# OpenUltrasound_Pulser.net
KiCad netlist of a schematic drawn in Altium Designer
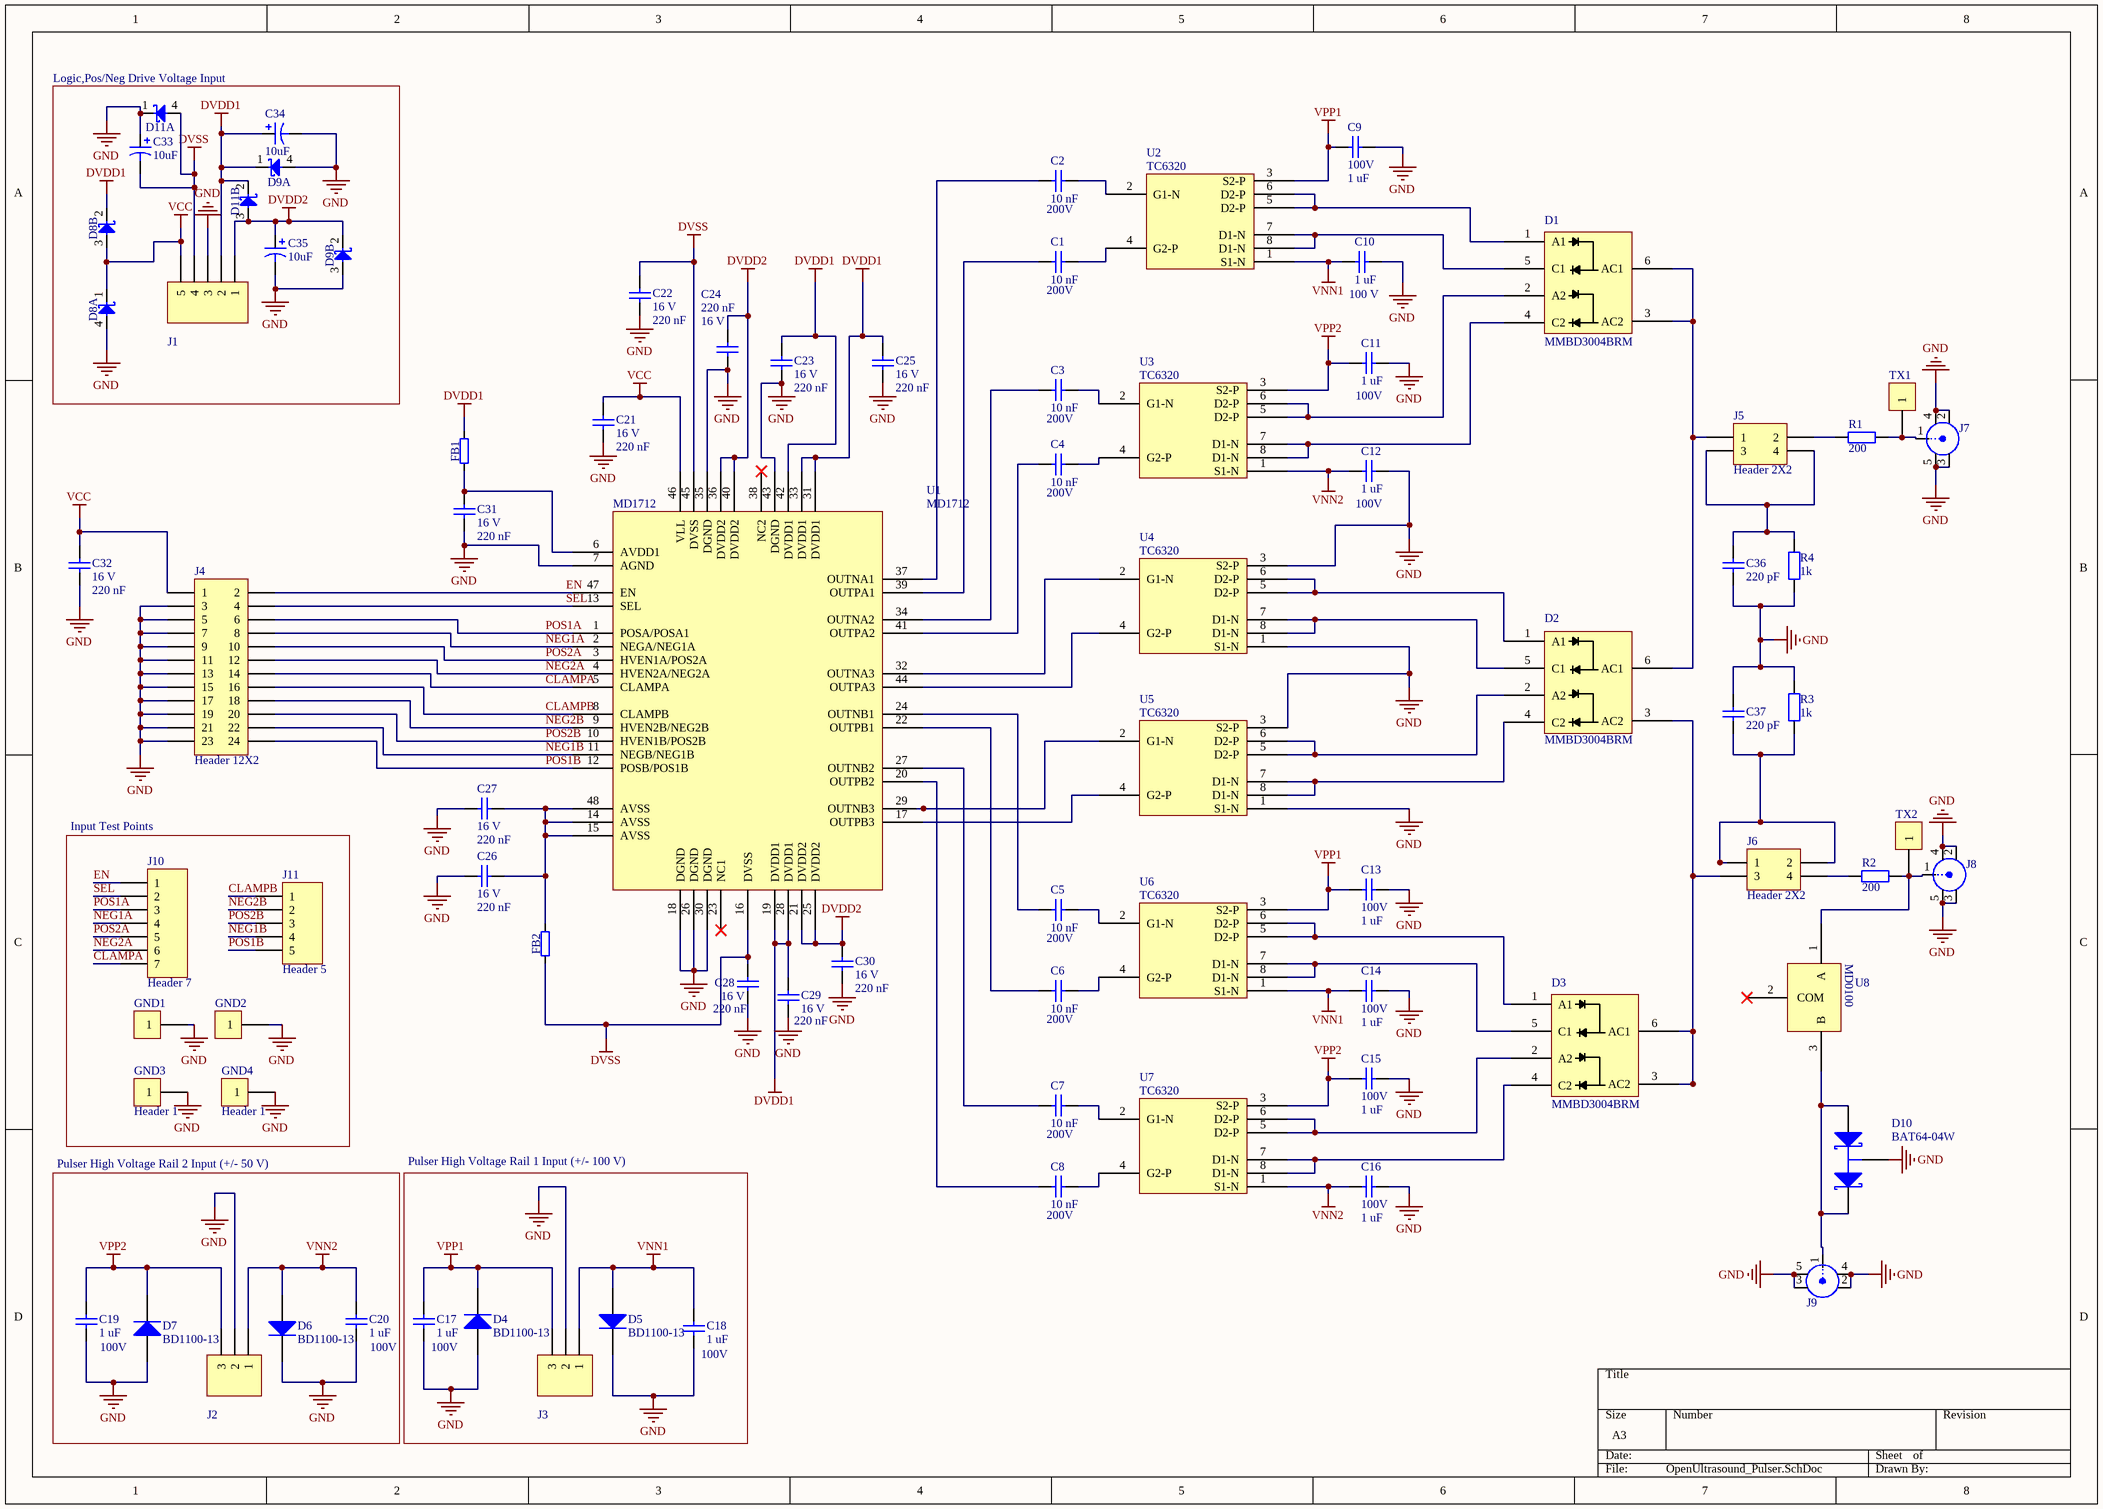
[diagram p0: OpenUltrasound_Pulser.SchDoc]

(export (version "E")
  (design (tool "Eeschema 10.0.6"))
  (components
    (comp (ref "C1")
      (value "200V")
      (footprint "CAP1608X100N")
      (description "Capacitor")
      (fields (field (name "ALTIUM_VALUE") "10 nF"))
      (libsource (lib "OpenUltrasound_Components") (part "CAP0603"))
    )
    (comp (ref "C2")
      (value "200V")
      (footprint "CAP1608X100N")
      (description "Capacitor")
      (fields (field (name "ALTIUM_VALUE") "10 nF"))
      (libsource (lib "OpenUltrasound_Components") (part "CAP0603"))
    )
    (comp (ref "C3")
      (value "200V")
      (footprint "CAP1608X100N")
      (description "Capacitor")
      (fields (field (name "ALTIUM_VALUE") "10 nF"))
      (libsource (lib "OpenUltrasound_Components") (part "CAP0603"))
    )
    (comp (ref "C4")
      (value "200V")
      (footprint "CAP1608X100N")
      (description "Capacitor")
      (fields (field (name "ALTIUM_VALUE") "10 nF"))
      (libsource (lib "OpenUltrasound_Components") (part "CAP0603"))
    )
    (comp (ref "C5")
      (value "200V")
      (footprint "CAP1608X100N")
      (description "Capacitor")
      (fields (field (name "ALTIUM_VALUE") "10 nF"))
      (libsource (lib "OpenUltrasound_Components") (part "CAP0603"))
    )
    (comp (ref "C6")
      (value "200V")
      (footprint "CAP1608X100N")
      (description "Capacitor")
      (fields (field (name "ALTIUM_VALUE") "10 nF"))
      (libsource (lib "OpenUltrasound_Components") (part "CAP0603"))
    )
    (comp (ref "C7")
      (value "200V")
      (footprint "CAP1608X100N")
      (description "Capacitor")
      (fields (field (name "ALTIUM_VALUE") "10 nF"))
      (libsource (lib "OpenUltrasound_Components") (part "CAP0603"))
    )
    (comp (ref "C8")
      (value "200V")
      (footprint "CAP1608X100N")
      (description "Capacitor")
      (fields (field (name "ALTIUM_VALUE") "10 nF"))
      (libsource (lib "OpenUltrasound_Components") (part "CAP0603"))
    )
    (comp (ref "C9")
      (value "100V")
      (footprint "CAP3216X180N")
      (description "Capacitor")
      (fields (field (name "ALTIUM_VALUE") "1 uF"))
      (libsource (lib "OpenUltrasound_Components") (part "CAP1206"))
    )
    (comp (ref "C10")
      (value "100 V")
      (footprint "CAP3216X180N")
      (description "Capacitor")
      (fields (field (name "ALTIUM_VALUE") "1 uF"))
      (libsource (lib "OpenUltrasound_Components") (part "CAP1206"))
    )
    (comp (ref "C11")
      (value "100V")
      (footprint "CAP3216X180N")
      (description "Capacitor")
      (fields (field (name "ALTIUM_VALUE") "1 uF"))
      (libsource (lib "OpenUltrasound_Components") (part "CAP1206"))
    )
    (comp (ref "C12")
      (value "100V")
      (footprint "CAP3216X180N")
      (description "Capacitor")
      (fields (field (name "ALTIUM_VALUE") "1 uF"))
      (libsource (lib "OpenUltrasound_Components") (part "CAP1206"))
    )
    (comp (ref "C13")
      (value "100V")
      (footprint "CAP3216X180N")
      (description "Capacitor")
      (fields (field (name "ALTIUM_VALUE") "1 uF"))
      (libsource (lib "OpenUltrasound_Components") (part "CAP1206"))
    )
    (comp (ref "C14")
      (value "100V")
      (footprint "CAP3216X180N")
      (description "Capacitor")
      (fields (field (name "ALTIUM_VALUE") "1 uF"))
      (libsource (lib "OpenUltrasound_Components") (part "CAP1206"))
    )
    (comp (ref "C15")
      (value "100V")
      (footprint "CAP3216X180N")
      (description "Capacitor")
      (fields (field (name "ALTIUM_VALUE") "1 uF"))
      (libsource (lib "OpenUltrasound_Components") (part "CAP1206"))
    )
    (comp (ref "C16")
      (value "100V")
      (footprint "CAP3216X180N")
      (description "Capacitor")
      (fields (field (name "ALTIUM_VALUE") "1 uF"))
      (libsource (lib "OpenUltrasound_Components") (part "CAP1206"))
    )
    (comp (ref "C17")
      (value "100V")
      (footprint "CAP3216X180N")
      (description "Capacitor")
      (fields (field (name "ALTIUM_VALUE") "1 uF"))
      (libsource (lib "OpenUltrasound_Components") (part "CAP1206"))
    )
    (comp (ref "C18")
      (value "100V")
      (footprint "CAP3216X180N")
      (description "Capacitor")
      (fields (field (name "ALTIUM_VALUE") "1 uF"))
      (libsource (lib "OpenUltrasound_Components") (part "CAP1206"))
    )
    (comp (ref "C19")
      (value "100V")
      (footprint "CAP3216X180N")
      (description "Capacitor")
      (fields (field (name "ALTIUM_VALUE") "1 uF"))
      (libsource (lib "OpenUltrasound_Components") (part "CAP1206"))
    )
    (comp (ref "C20")
      (value "100V")
      (footprint "CAP3216X180N")
      (description "Capacitor")
      (fields (field (name "ALTIUM_VALUE") "1 uF"))
      (libsource (lib "OpenUltrasound_Components") (part "CAP1206"))
    )
    (comp (ref "C21")
      (value "16 V")
      (footprint "CAP1608X100N")
      (description "Capacitor")
      (fields (field (name "ALTIUM_VALUE") "220 nF"))
      (libsource (lib "OpenUltrasound_Components") (part "CAP0603"))
    )
    (comp (ref "C22")
      (value "16 V")
      (footprint "CAP1608X100N")
      (description "Capacitor")
      (fields (field (name "ALTIUM_VALUE") "220 nF"))
      (libsource (lib "OpenUltrasound_Components") (part "CAP0603"))
    )
    (comp (ref "C23")
      (value "16 V")
      (footprint "CAP1608X100N")
      (description "Capacitor")
      (fields (field (name "ALTIUM_VALUE") "220 nF"))
      (libsource (lib "OpenUltrasound_Components") (part "CAP0603"))
    )
    (comp (ref "C24")
      (value "16 V")
      (footprint "CAP1608X100N")
      (description "Capacitor")
      (fields (field (name "ALTIUM_VALUE") "220 nF"))
      (libsource (lib "OpenUltrasound_Components") (part "CAP0603"))
    )
    (comp (ref "C25")
      (value "16 V")
      (footprint "CAP1608X100N")
      (description "Capacitor")
      (fields (field (name "ALTIUM_VALUE") "220 nF"))
      (libsource (lib "OpenUltrasound_Components") (part "CAP0603"))
    )
    (comp (ref "C26")
      (value "16 V")
      (footprint "CAP1608X100N")
      (description "Capacitor")
      (fields (field (name "ALTIUM_VALUE") "220 nF"))
      (libsource (lib "OpenUltrasound_Components") (part "CAP0603"))
    )
    (comp (ref "C27")
      (value "16 V")
      (footprint "CAP1608X100N")
      (description "Capacitor")
      (fields (field (name "ALTIUM_VALUE") "220 nF"))
      (libsource (lib "OpenUltrasound_Components") (part "CAP0603"))
    )
    (comp (ref "C28")
      (value "16 V")
      (footprint "CAP1608X100N")
      (description "Capacitor")
      (fields (field (name "ALTIUM_VALUE") "220 nF"))
      (libsource (lib "OpenUltrasound_Components") (part "CAP0603"))
    )
    (comp (ref "C29")
      (value "16 V")
      (footprint "CAP1608X100N")
      (description "Capacitor")
      (fields (field (name "ALTIUM_VALUE") "220 nF"))
      (libsource (lib "OpenUltrasound_Components") (part "CAP0603"))
    )
    (comp (ref "C30")
      (value "16 V")
      (footprint "CAP1608X100N")
      (description "Capacitor")
      (fields (field (name "ALTIUM_VALUE") "220 nF"))
      (libsource (lib "OpenUltrasound_Components") (part "CAP0603"))
    )
    (comp (ref "C31")
      (value "16 V")
      (footprint "CAP1608X100N")
      (description "Capacitor")
      (fields (field (name "ALTIUM_VALUE") "220 nF"))
      (libsource (lib "OpenUltrasound_Components") (part "CAP0603"))
    )
    (comp (ref "C32")
      (value "16 V")
      (footprint "CAP1608X100N")
      (description "Capacitor")
      (fields (field (name "ALTIUM_VALUE") "220 nF"))
      (libsource (lib "OpenUltrasound_Components") (part "CAP0603"))
    )
    (comp (ref "C33")
      (value "10uF")
      (footprint "CAPAE530X540N")
      (description "Polarized Capacitor (Radial Can SMD)")
      (libsource (lib "OpenUltrasound_Components") (part "CAP POL"))
    )
    (comp (ref "C34")
      (value "10uF")
      (footprint "CAPAE530X540N")
      (description "Polarized Capacitor (Radial Can SMD)")
      (libsource (lib "OpenUltrasound_Components") (part "CAP POL"))
    )
    (comp (ref "C35")
      (value "10uF")
      (footprint "CAPAE530X540N")
      (description "Polarized Capacitor (Radial Can SMD)")
      (libsource (lib "OpenUltrasound_Components") (part "CAP POL"))
    )
    (comp (ref "C36")
      (value "220 pF")
      (footprint "CAP1608X100N")
      (description "Capacitor")
      (libsource (lib "OpenUltrasound_Components") (part "CAP0603"))
    )
    (comp (ref "C37")
      (value "220 pF")
      (footprint "CAP1608X100N")
      (description "Capacitor")
      (libsource (lib "OpenUltrasound_Components") (part "CAP0603"))
    )
    (comp (ref "D1")
      (value "MMBD3004BRM")
      (footprint "SOT26A-6AN")
      (description "High Voltage Surface Mount Switching Diode Array")
      (libsource (lib "OpenUltrasound_Components") (part "MMBD3004BRM"))
    )
    (comp (ref "D2")
      (value "MMBD3004BRM")
      (footprint "SOT26A-6AN")
      (description "High Voltage Surface Mount Switching Diode Array")
      (libsource (lib "OpenUltrasound_Components") (part "MMBD3004BRM"))
    )
    (comp (ref "D3")
      (value "MMBD3004BRM")
      (footprint "SOT26A-6AN")
      (description "High Voltage Surface Mount Switching Diode Array")
      (libsource (lib "OpenUltrasound_Components") (part "MMBD3004BRM"))
    )
    (comp (ref "D4")
      (value "BD1100-13")
      (footprint "ST DO214AC SMA")
      (libsource (lib "OpenUltrasound_Components") (part "BD1100-13"))
    )
    (comp (ref "D5")
      (value "BD1100-13")
      (footprint "ST DO214AC SMA")
      (libsource (lib "OpenUltrasound_Components") (part "BD1100-13"))
    )
    (comp (ref "D6")
      (value "BD1100-13")
      (footprint "ST DO214AC SMA")
      (libsource (lib "OpenUltrasound_Components") (part "BD1100-13"))
    )
    (comp (ref "D7")
      (value "BD1100-13")
      (footprint "ST DO214AC SMA")
      (libsource (lib "OpenUltrasound_Components") (part "BD1100-13"))
    )
    (comp (ref "D8")
      (value "~")
      (footprint "SOT143L")
      (description "Serial Schottky Diode")
      (libsource (lib "OpenUltrasound_Components") (part "Diode Schottky x2 A4C1_A3C2"))
    )
    (comp (ref "D9")
      (value "~")
      (footprint "SOT143L")
      (description "Serial Schottky Diode")
      (libsource (lib "OpenUltrasound_Components") (part "Diode Schottky x2 A4C1_A3C2"))
    )
    (comp (ref "D10")
      (value "BAT64-04W")
      (footprint "SOT-323")
      (description "Silicon AF Schottky Diode for Low-Loss, Fast-Recovery, Meter Protection")
      (fields (field (name "PUBLISHER") "Altium Limited"))
      (libsource (lib "OpenUltrasound_Components") (part "BAT64-04W"))
    )
    (comp (ref "D11")
      (value "~")
      (footprint "SOT143L")
      (description "Serial Schottky Diode")
      (libsource (lib "OpenUltrasound_Components") (part "Diode Schottky x2 A4C1_A3C2"))
    )
    (comp (ref "FB1")
      (value "~")
      (footprint "CAP1608X85N")
      (description "Ferrite Bead")
      (libsource (lib "OpenUltrasound_Components") (part "Ferrite Bead"))
    )
    (comp (ref "FB2")
      (value "~")
      (footprint "CAP1608X85N")
      (description "Ferrite Bead")
      (libsource (lib "OpenUltrasound_Components") (part "Ferrite Bead"))
    )
    (comp (ref "GND1")
      (value "Header 1")
      (footprint "HDR1X1")
      (description "Header, 1-Pin")
      (fields (field (name "PUBLISHER") "Altium Limited"))
      (libsource (lib "") (part "Header 1_1"))
    )
    (comp (ref "GND2")
      (value "Header 1")
      (footprint "HDR1X1")
      (description "Header, 1-Pin")
      (fields (field (name "PUBLISHER") "Altium Limited"))
      (libsource (lib "") (part "Header 1_1"))
    )
    (comp (ref "GND3")
      (value "Header 1")
      (footprint "HDR1X1")
      (description "Header, 1-Pin")
      (fields (field (name "PUBLISHER") "Altium Limited"))
      (libsource (lib "") (part "Header 1_1"))
    )
    (comp (ref "GND4")
      (value "Header 1")
      (footprint "HDR1X1")
      (description "Header, 1-Pin")
      (fields (field (name "PUBLISHER") "Altium Limited"))
      (libsource (lib "") (part "Header 1_1"))
    )
    (comp (ref "J1")
      (value "Header 5 - pin")
      (footprint "B5B-XH-A")
      (description "Header, 5-pin")
      (fields (field (name "PUBLISHER") "Altium Limited"))
      (libsource (lib "OpenUltrasound_Components") (part "B5B-XH-A"))
    )
    (comp (ref "J2")
      (value "Header 3 - pin")
      (footprint "B3B-XH-A")
      (description "Header, 3-pin")
      (fields (field (name "PUBLISHER") "Altium Limited"))
      (libsource (lib "OpenUltrasound_Components") (part "B3B-XH-A"))
    )
    (comp (ref "J3")
      (value "Header 3 - pin")
      (footprint "B3B-XH-A")
      (description "Header, 3-pin")
      (fields (field (name "PUBLISHER") "Altium Limited"))
      (libsource (lib "OpenUltrasound_Components") (part "B3B-XH-A"))
    )
    (comp (ref "J4")
      (value "Header 12X2")
      (footprint "HDR2X12")
      (description "Header, 12-Pin, Dual row")
      (fields (field (name "PUBLISHER") "Altium Limited"))
      (libsource (lib "OpenUltrasound_Components") (part "Header 12X2"))
    )
    (comp (ref "J5")
      (value "Header 2X2")
      (footprint "HDR2X2")
      (description "Header, 2-Pin, Dual row")
      (fields (field (name "PUBLISHER") "Altium Limited"))
      (libsource (lib "OpenUltrasound_Components") (part "Header 2X2"))
    )
    (comp (ref "J6")
      (value "Header 2X2")
      (footprint "HDR2X2")
      (description "Header, 2-Pin, Dual row")
      (fields (field (name "PUBLISHER") "Altium Limited"))
      (libsource (lib "OpenUltrasound_Components") (part "Header 2X2"))
    )
    (comp (ref "J7")
      (value "SMA_EDGE_MOUNT")
      (footprint "SMA-J-P-X-ST-EM1")
      (description "BNC Elbow Connector")
      (fields (field (name "PUBLISHER") "Altium Limited"))
      (libsource (lib "OpenUltrasound_Components") (part "SMA_EDGE_MOUNT"))
    )
    (comp (ref "J8")
      (value "SMA_EDGE_MOUNT")
      (footprint "SMA-J-P-X-ST-EM1")
      (description "BNC Elbow Connector")
      (fields (field (name "PUBLISHER") "Altium Limited"))
      (libsource (lib "OpenUltrasound_Components") (part "SMA_EDGE_MOUNT"))
    )
    (comp (ref "J9")
      (value "SMA_EDGE_MOUNT")
      (footprint "SMA-J-P-X-ST-EM1")
      (description "BNC Elbow Connector")
      (fields (field (name "PUBLISHER") "Altium Limited"))
      (libsource (lib "OpenUltrasound_Components") (part "SMA_EDGE_MOUNT"))
    )
    (comp (ref "J10")
      (value "Header 7")
      (footprint "HDR1X7")
      (description "Header, 7-Pin")
      (fields (field (name "PUBLISHER") "Altium Limited"))
      (libsource (lib "OpenUltrasound_Components") (part "Header 7"))
    )
    (comp (ref "J11")
      (value "Header 5")
      (footprint "HDR1X5")
      (description "Header, 5-Pin")
      (fields (field (name "PUBLISHER") "Altium Limited"))
      (libsource (lib "OpenUltrasound_Components") (part "Header 5"))
    )
    (comp (ref "R1")
      (value "200")
      (footprint "RESC2012X70N-0805")
      (description "Resistor")
      (libsource (lib "OpenUltrasound_Components") (part "RES0805"))
    )
    (comp (ref "R2")
      (value "200")
      (footprint "RESC2012X70N-0805")
      (description "Resistor")
      (libsource (lib "OpenUltrasound_Components") (part "RES0805"))
    )
    (comp (ref "R3")
      (value "1k")
      (footprint "RESC3216X80N-1206")
      (description "Resistor")
      (libsource (lib "OpenUltrasound_Components") (part "RES1206"))
    )
    (comp (ref "R4")
      (value "1k")
      (footprint "RESC3216X80N-1206")
      (description "Resistor")
      (libsource (lib "OpenUltrasound_Components") (part "RES1206"))
    )
    (comp (ref "TX1")
      (value "Header 1")
      (footprint "HDR1X1")
      (description "Header, 1-Pin")
      (fields (field (name "PUBLISHER") "Altium Limited"))
      (libsource (lib "OpenUltrasound_Components") (part "Header 1"))
    )
    (comp (ref "TX2")
      (value "Header 1")
      (footprint "HDR1X1")
      (description "Header, 1-Pin")
      (fields (field (name "PUBLISHER") "Altium Limited"))
      (libsource (lib "OpenUltrasound_Components") (part "Header 1"))
    )
    (comp (ref "U1")
      (value "MD1712")
      (footprint "OpenUltrasound_PcbLib:LQFP-48")
      (description "High Speed, Integrated Ultrasound Driver IC")
      (libsource (lib "OpenUltrasound_Schlib") (part "MD1712"))
    )
    (comp (ref "U2")
      (value "TC6320")
      (footprint "OpenUltrasound_PcbLib:SOIC127P600X175-8N")
      (libsource (lib "OpenUltrasound_Components") (part "TC6320"))
    )
    (comp (ref "U3")
      (value "TC6320")
      (footprint "OpenUltrasound_PcbLib:SOIC127P600X175-8N")
      (libsource (lib "OpenUltrasound_Components") (part "TC6320"))
    )
    (comp (ref "U4")
      (value "TC6320")
      (footprint "OpenUltrasound_PcbLib:SOIC127P600X175-8N")
      (libsource (lib "OpenUltrasound_Components") (part "TC6320"))
    )
    (comp (ref "U5")
      (value "TC6320")
      (footprint "OpenUltrasound_PcbLib:SOIC127P600X175-8N")
      (libsource (lib "OpenUltrasound_Components") (part "TC6320"))
    )
    (comp (ref "U6")
      (value "TC6320")
      (footprint "OpenUltrasound_PcbLib:SOIC127P600X175-8N")
      (libsource (lib "OpenUltrasound_Components") (part "TC6320"))
    )
    (comp (ref "U7")
      (value "TC6320")
      (footprint "OpenUltrasound_PcbLib:SOIC127P600X175-8N")
      (libsource (lib "OpenUltrasound_Components") (part "TC6320"))
    )
    (comp (ref "U8")
      (value "MD0100")
      (footprint "SOT89")
      (description "High voltage protection T/R switch")
      (libsource (lib "OpenUltrasound_Components") (part "MD0100"))
    )
  )
  (nets
    (net (code "1") (name "/CLAMPA") (class "Default")
      (node (ref "J10") (pin "7") (pinfunction "7_7") (pintype "passive"))
      (node (ref "J4") (pin "14") (pinfunction "14_14") (pintype "passive"))
      (node (ref "U1") (pin "5") (pinfunction "CLAMPA_5") (pintype "passive"))
    )
    (net (code "2") (name "/CLAMPB") (class "Default")
      (node (ref "J11") (pin "1") (pinfunction "1_1") (pintype "passive"))
      (node (ref "J4") (pin "16") (pinfunction "16_16") (pintype "passive"))
      (node (ref "U1") (pin "8") (pinfunction "CLAMPB_8") (pintype "passive"))
    )
    (net (code "3") (name "/EN") (class "Default")
      (node (ref "J10") (pin "1") (pinfunction "1_1") (pintype "passive"))
      (node (ref "J4") (pin "2") (pinfunction "2_2") (pintype "passive"))
      (node (ref "U1") (pin "47") (pinfunction "EN_47") (pintype "passive"))
    )
    (net (code "4") (name "/NEG1A") (class "Default")
      (node (ref "J10") (pin "4") (pinfunction "4_4") (pintype "passive"))
      (node (ref "J4") (pin "8") (pinfunction "8_8") (pintype "passive"))
      (node (ref "U1") (pin "2") (pinfunction "NEGA/NEG1A_2") (pintype "passive"))
    )
    (net (code "5") (name "/NEG1B") (class "Default")
      (node (ref "J11") (pin "4") (pinfunction "4_4") (pintype "passive"))
      (node (ref "J4") (pin "22") (pinfunction "22_22") (pintype "passive"))
      (node (ref "U1") (pin "11") (pinfunction "NEGB/NEG1B_11") (pintype "passive"))
    )
    (net (code "6") (name "/NEG2A") (class "Default")
      (node (ref "J10") (pin "6") (pinfunction "6_6") (pintype "passive"))
      (node (ref "J4") (pin "12") (pinfunction "12_12") (pintype "passive"))
      (node (ref "U1") (pin "4") (pinfunction "HVEN2A/NEG2A_4") (pintype "passive"))
    )
    (net (code "7") (name "/NEG2B") (class "Default")
      (node (ref "J11") (pin "2") (pinfunction "2_2") (pintype "passive"))
      (node (ref "J4") (pin "18") (pinfunction "18_18") (pintype "passive"))
      (node (ref "U1") (pin "9") (pinfunction "HVEN2B/NEG2B_9") (pintype "passive"))
    )
    (net (code "8") (name "/POS1A") (class "Default")
      (node (ref "J10") (pin "3") (pinfunction "3_3") (pintype "passive"))
      (node (ref "J4") (pin "6") (pinfunction "6_6") (pintype "passive"))
      (node (ref "U1") (pin "1") (pinfunction "POSA/POSA1_1") (pintype "passive"))
    )
    (net (code "9") (name "/POS1B") (class "Default")
      (node (ref "J11") (pin "5") (pinfunction "5_5") (pintype "passive"))
      (node (ref "J4") (pin "24") (pinfunction "24_24") (pintype "passive"))
      (node (ref "U1") (pin "12") (pinfunction "POSB/POS1B_12") (pintype "passive"))
    )
    (net (code "10") (name "/POS2A") (class "Default")
      (node (ref "J10") (pin "5") (pinfunction "5_5") (pintype "passive"))
      (node (ref "J4") (pin "10") (pinfunction "10_10") (pintype "passive"))
      (node (ref "U1") (pin "3") (pinfunction "HVEN1A/POS2A_3") (pintype "passive"))
    )
    (net (code "11") (name "/POS2B") (class "Default")
      (node (ref "J11") (pin "3") (pinfunction "3_3") (pintype "passive"))
      (node (ref "J4") (pin "20") (pinfunction "20_20") (pintype "passive"))
      (node (ref "U1") (pin "10") (pinfunction "HVEN1B/POS2B_10") (pintype "passive"))
    )
    (net (code "12") (name "/SEL") (class "Default")
      (node (ref "J10") (pin "2") (pinfunction "2_2") (pintype "passive"))
      (node (ref "J4") (pin "4") (pinfunction "4_4") (pintype "passive"))
      (node (ref "U1") (pin "13") (pinfunction "SEL_13") (pintype "passive"))
    )
    (net (code "13") (name "DVDD1") (class "Default")
      (node (ref "C23") (pin "2") (pinfunction "2_2") (pintype "passive"))
      (node (ref "C25") (pin "2") (pinfunction "2_2") (pintype "passive"))
      (node (ref "C29") (pin "2") (pinfunction "2_2") (pintype "passive"))
      (node (ref "C34") (pin "1") (pinfunction "1_1") (pintype "passive"))
      (node (ref "D11") (pin "2") (pinfunction "C2_2") (pintype "passive"))
      (node (ref "D8") (pin "2") (pinfunction "C2_2") (pintype "passive"))
      (node (ref "D9") (pin "1") (pinfunction "A2_1") (pintype "passive"))
      (node (ref "FB1") (pin "2") (pinfunction "2_2") (pintype "passive"))
      (node (ref "J1") (pin "2") (pinfunction "2_2") (pintype "passive"))
      (node (ref "U1") (pin "19") (pinfunction "DVDD1_19") (pintype "passive"))
      (node (ref "U1") (pin "28") (pinfunction "DVDD1_28") (pintype "passive"))
      (node (ref "U1") (pin "31") (pinfunction "DVDD1_31") (pintype "passive"))
      (node (ref "U1") (pin "33") (pinfunction "DVDD1_33") (pintype "passive"))
      (node (ref "U1") (pin "42") (pinfunction "DVDD1_42") (pintype "passive"))
    )
    (net (code "14") (name "DVDD2") (class "Default")
      (node (ref "C24") (pin "2") (pinfunction "2_2") (pintype "passive"))
      (node (ref "C30") (pin "2") (pinfunction "2_2") (pintype "passive"))
      (node (ref "C35") (pin "1") (pinfunction "1_1") (pintype "passive"))
      (node (ref "D11") (pin "3") (pinfunction "A1_3") (pintype "passive"))
      (node (ref "D9") (pin "2") (pinfunction "C2_2") (pintype "passive"))
      (node (ref "J1") (pin "1") (pinfunction "1_1") (pintype "passive"))
      (node (ref "U1") (pin "21") (pinfunction "DVDD2_21") (pintype "power_in"))
      (node (ref "U1") (pin "25") (pinfunction "DVDD2_25") (pintype "passive"))
      (node (ref "U1") (pin "36") (pinfunction "DVDD2_36") (pintype "passive"))
      (node (ref "U1") (pin "40") (pinfunction "DVDD2_40") (pintype "passive"))
    )
    (net (code "15") (name "DVSS") (class "Default")
      (node (ref "C22") (pin "2") (pinfunction "2_2") (pintype "passive"))
      (node (ref "C28") (pin "2") (pinfunction "2_2") (pintype "passive"))
      (node (ref "C33") (pin "2") (pinfunction "2_2") (pintype "passive"))
      (node (ref "D11") (pin "4") (pinfunction "C1_4") (pintype "passive"))
      (node (ref "FB2") (pin "1") (pinfunction "1_1") (pintype "passive"))
      (node (ref "J1") (pin "4") (pinfunction "4_4") (pintype "passive"))
      (node (ref "U1") (pin "16") (pinfunction "DVSS_16") (pintype "passive"))
      (node (ref "U1") (pin "45") (pinfunction "DVSS_45") (pintype "passive"))
    )
    (net (code "16") (name "GND") (class "Default")
      (node (ref "C10") (pin "2") (pinfunction "2_2") (pintype "passive"))
      (node (ref "C11") (pin "1") (pinfunction "1_1") (pintype "passive"))
      (node (ref "C12") (pin "1") (pinfunction "1_1") (pintype "passive"))
      (node (ref "C13") (pin "1") (pinfunction "1_1") (pintype "passive"))
      (node (ref "C14") (pin "1") (pinfunction "1_1") (pintype "passive"))
      (node (ref "C15") (pin "1") (pinfunction "1_1") (pintype "passive"))
      (node (ref "C16") (pin "1") (pinfunction "1_1") (pintype "passive"))
      (node (ref "C17") (pin "1") (pinfunction "1_1") (pintype "passive"))
      (node (ref "C18") (pin "1") (pinfunction "1_1") (pintype "passive"))
      (node (ref "C19") (pin "1") (pinfunction "1_1") (pintype "passive"))
      (node (ref "C20") (pin "1") (pinfunction "1_1") (pintype "passive"))
      (node (ref "C21") (pin "1") (pinfunction "1_1") (pintype "passive"))
      (node (ref "C22") (pin "1") (pinfunction "1_1") (pintype "passive"))
      (node (ref "C23") (pin "1") (pinfunction "1_1") (pintype "passive"))
      (node (ref "C24") (pin "1") (pinfunction "1_1") (pintype "passive"))
      (node (ref "C25") (pin "1") (pinfunction "1_1") (pintype "passive"))
      (node (ref "C26") (pin "2") (pinfunction "2_2") (pintype "passive"))
      (node (ref "C27") (pin "2") (pinfunction "2_2") (pintype "passive"))
      (node (ref "C28") (pin "1") (pinfunction "1_1") (pintype "passive"))
      (node (ref "C29") (pin "1") (pinfunction "1_1") (pintype "passive"))
      (node (ref "C30") (pin "1") (pinfunction "1_1") (pintype "passive"))
      (node (ref "C31") (pin "1") (pinfunction "1_1") (pintype "passive"))
      (node (ref "C32") (pin "1") (pinfunction "1_1") (pintype "passive"))
      (node (ref "C33") (pin "1") (pinfunction "1_1") (pintype "passive"))
      (node (ref "C34") (pin "2") (pinfunction "2_2") (pintype "passive"))
      (node (ref "C35") (pin "2") (pinfunction "2_2") (pintype "passive"))
      (node (ref "C36") (pin "1") (pinfunction "1_1") (pintype "passive"))
      (node (ref "C37") (pin "2") (pinfunction "2_2") (pintype "passive"))
      (node (ref "C9") (pin "1") (pinfunction "1_1") (pintype "passive"))
      (node (ref "D10") (pin "3") (pinfunction "C_3") (pintype "passive"))
      (node (ref "D11") (pin "1") (pinfunction "A2_1") (pintype "passive"))
      (node (ref "D4") (pin "1") (pinfunction "1_1") (pintype "passive"))
      (node (ref "D5") (pin "2") (pinfunction "2_2") (pintype "passive"))
      (node (ref "D6") (pin "2") (pinfunction "2_2") (pintype "passive"))
      (node (ref "D7") (pin "1") (pinfunction "1_1") (pintype "passive"))
      (node (ref "D8") (pin "4") (pinfunction "C1_4") (pintype "passive"))
      (node (ref "D9") (pin "3") (pinfunction "A1_3") (pintype "passive"))
      (node (ref "D9") (pin "4") (pinfunction "C1_4") (pintype "passive"))
      (node (ref "GND1") (pin "1") (pinfunction "1_1") (pintype "passive"))
      (node (ref "GND2") (pin "1") (pinfunction "1_1") (pintype "passive"))
      (node (ref "GND3") (pin "1") (pinfunction "1_1") (pintype "passive"))
      (node (ref "GND4") (pin "1") (pinfunction "1_1") (pintype "passive"))
      (node (ref "J1") (pin "3") (pinfunction "3_3") (pintype "power_in"))
      (node (ref "J2") (pin "2") (pinfunction "2_2") (pintype "passive"))
      (node (ref "J3") (pin "2") (pinfunction "2_2") (pintype "passive"))
      (node (ref "J4") (pin "11") (pinfunction "11_11") (pintype "passive"))
      (node (ref "J4") (pin "13") (pinfunction "13_13") (pintype "passive"))
      (node (ref "J4") (pin "15") (pinfunction "15_15") (pintype "passive"))
      (node (ref "J4") (pin "17") (pinfunction "17_17") (pintype "passive"))
      (node (ref "J4") (pin "19") (pinfunction "19_19") (pintype "passive"))
      (node (ref "J4") (pin "21") (pinfunction "21_21") (pintype "passive"))
      (node (ref "J4") (pin "23") (pinfunction "23_23") (pintype "passive"))
      (node (ref "J4") (pin "3") (pinfunction "3_3") (pintype "passive"))
      (node (ref "J4") (pin "5") (pinfunction "5_5") (pintype "passive"))
      (node (ref "J4") (pin "7") (pinfunction "7_7") (pintype "passive"))
      (node (ref "J4") (pin "9") (pinfunction "9_9") (pintype "passive"))
      (node (ref "J7") (pin "2") (pinfunction "Y_2") (pintype "passive"))
      (node (ref "J7") (pin "3") (pinfunction "3_3") (pintype "passive"))
      (node (ref "J7") (pin "4") (pinfunction "4_4") (pintype "passive"))
      (node (ref "J7") (pin "5") (pinfunction "5_5") (pintype "passive"))
      (node (ref "J8") (pin "2") (pinfunction "Y_2") (pintype "passive"))
      (node (ref "J8") (pin "3") (pinfunction "3_3") (pintype "passive"))
      (node (ref "J8") (pin "4") (pinfunction "4_4") (pintype "passive"))
      (node (ref "J8") (pin "5") (pinfunction "5_5") (pintype "passive"))
      (node (ref "J9") (pin "2") (pinfunction "Y_2") (pintype "passive"))
      (node (ref "J9") (pin "3") (pinfunction "3_3") (pintype "passive"))
      (node (ref "J9") (pin "4") (pinfunction "4_4") (pintype "passive"))
      (node (ref "J9") (pin "5") (pinfunction "5_5") (pintype "passive"))
      (node (ref "R3") (pin "2") (pinfunction "2_2") (pintype "passive"))
      (node (ref "R4") (pin "1") (pinfunction "1_1") (pintype "passive"))
      (node (ref "U1") (pin "18") (pinfunction "DGND_18") (pintype "power_in"))
      (node (ref "U1") (pin "26") (pinfunction "DGND_26") (pintype "passive"))
      (node (ref "U1") (pin "30") (pinfunction "DGND_30") (pintype "passive"))
      (node (ref "U1") (pin "35") (pinfunction "DGND_35") (pintype "passive"))
      (node (ref "U1") (pin "43") (pinfunction "DGND_43") (pintype "passive"))
      (node (ref "U1") (pin "7") (pinfunction "AGND_7") (pintype "power_in"))
      (node (ref "U4") (pin "1") (pinfunction "S1-N_1") (pintype "passive"))
      (node (ref "U4") (pin "3") (pinfunction "S2-P_3") (pintype "passive"))
      (node (ref "U5") (pin "1") (pinfunction "S1-N_1") (pintype "passive"))
      (node (ref "U5") (pin "3") (pinfunction "S2-P_3") (pintype "passive"))
    )
    (net (code "17") (name "Net-(C26-Pad1)") (class "Default")
      (node (ref "C26") (pin "1") (pinfunction "1_1") (pintype "passive"))
      (node (ref "C27") (pin "1") (pinfunction "1_1") (pintype "passive"))
      (node (ref "FB2") (pin "2") (pinfunction "2_2") (pintype "passive"))
      (node (ref "U1") (pin "14") (pinfunction "AVSS_14") (pintype "power_in"))
      (node (ref "U1") (pin "15") (pinfunction "AVSS_15") (pintype "power_in"))
      (node (ref "U1") (pin "48") (pinfunction "AVSS_48") (pintype "power_in"))
    )
    (net (code "18") (name "Net-(C36-Pad2)") (class "Default")
      (node (ref "C36") (pin "2") (pinfunction "2_2") (pintype "passive"))
      (node (ref "J5") (pin "3") (pinfunction "3_3") (pintype "passive"))
      (node (ref "J5") (pin "4") (pinfunction "4_4") (pintype "passive"))
      (node (ref "R4") (pin "2") (pinfunction "2_2") (pintype "passive"))
    )
    (net (code "19") (name "Net-(C37-Pad1)") (class "Default")
      (node (ref "C37") (pin "1") (pinfunction "1_1") (pintype "passive"))
      (node (ref "J6") (pin "1") (pinfunction "1_1") (pintype "passive"))
      (node (ref "J6") (pin "2") (pinfunction "2_2") (pintype "passive"))
      (node (ref "R3") (pin "1") (pinfunction "1_1") (pintype "passive"))
    )
    (net (code "20") (name "Net-(D1-A1)") (class "Default")
      (node (ref "D1") (pin "1") (pinfunction "A1_1") (pintype "passive"))
      (node (ref "U2") (pin "5") (pinfunction "D2-P_5") (pintype "passive"))
      (node (ref "U2") (pin "6") (pinfunction "D2-P_6") (pintype "passive"))
    )
    (net (code "21") (name "Net-(D1-A2)") (class "Default")
      (node (ref "D1") (pin "2") (pinfunction "A2_2") (pintype "passive"))
      (node (ref "U3") (pin "5") (pinfunction "D2-P_5") (pintype "passive"))
      (node (ref "U3") (pin "6") (pinfunction "D2-P_6") (pintype "passive"))
    )
    (net (code "22") (name "Net-(D1-AC1)") (class "Default")
      (node (ref "D1") (pin "3") (pinfunction "AC2_3") (pintype "passive"))
      (node (ref "D1") (pin "6") (pinfunction "AC1_6") (pintype "passive"))
      (node (ref "D2") (pin "6") (pinfunction "AC1_6") (pintype "passive"))
      (node (ref "J5") (pin "1") (pinfunction "1_1") (pintype "passive"))
    )
    (net (code "23") (name "Net-(D1-C1)") (class "Default")
      (node (ref "D1") (pin "5") (pinfunction "C1_5") (pintype "passive"))
      (node (ref "U2") (pin "7") (pinfunction "D1-N_7") (pintype "passive"))
      (node (ref "U2") (pin "8") (pinfunction "D1-N_8") (pintype "passive"))
    )
    (net (code "24") (name "Net-(D1-C2)") (class "Default")
      (node (ref "D1") (pin "4") (pinfunction "C2_4") (pintype "passive"))
      (node (ref "U3") (pin "7") (pinfunction "D1-N_7") (pintype "passive"))
      (node (ref "U3") (pin "8") (pinfunction "D1-N_8") (pintype "passive"))
    )
    (net (code "25") (name "Net-(D2-A1)") (class "Default")
      (node (ref "D2") (pin "1") (pinfunction "A1_1") (pintype "passive"))
      (node (ref "U4") (pin "5") (pinfunction "D2-P_5") (pintype "passive"))
      (node (ref "U4") (pin "6") (pinfunction "D2-P_6") (pintype "passive"))
    )
    (net (code "26") (name "Net-(D2-A2)") (class "Default")
      (node (ref "D2") (pin "2") (pinfunction "A2_2") (pintype "passive"))
      (node (ref "U5") (pin "5") (pinfunction "D2-P_5") (pintype "passive"))
      (node (ref "U5") (pin "6") (pinfunction "D2-P_6") (pintype "passive"))
    )
    (net (code "27") (name "Net-(D2-AC2)") (class "Default")
      (node (ref "D2") (pin "3") (pinfunction "AC2_3") (pintype "passive"))
      (node (ref "D3") (pin "3") (pinfunction "AC2_3") (pintype "passive"))
      (node (ref "D3") (pin "6") (pinfunction "AC1_6") (pintype "passive"))
      (node (ref "J6") (pin "3") (pinfunction "3_3") (pintype "passive"))
    )
    (net (code "28") (name "Net-(D2-C1)") (class "Default")
      (node (ref "D2") (pin "5") (pinfunction "C1_5") (pintype "passive"))
      (node (ref "U4") (pin "7") (pinfunction "D1-N_7") (pintype "passive"))
      (node (ref "U4") (pin "8") (pinfunction "D1-N_8") (pintype "passive"))
    )
    (net (code "29") (name "Net-(D2-C2)") (class "Default")
      (node (ref "D2") (pin "4") (pinfunction "C2_4") (pintype "passive"))
      (node (ref "U5") (pin "7") (pinfunction "D1-N_7") (pintype "passive"))
      (node (ref "U5") (pin "8") (pinfunction "D1-N_8") (pintype "passive"))
    )
    (net (code "30") (name "Net-(D3-A1)") (class "Default")
      (node (ref "D3") (pin "1") (pinfunction "A1_1") (pintype "passive"))
      (node (ref "U6") (pin "5") (pinfunction "D2-P_5") (pintype "passive"))
      (node (ref "U6") (pin "6") (pinfunction "D2-P_6") (pintype "passive"))
    )
    (net (code "31") (name "Net-(D3-A2)") (class "Default")
      (node (ref "D3") (pin "2") (pinfunction "A2_2") (pintype "passive"))
      (node (ref "U7") (pin "5") (pinfunction "D2-P_5") (pintype "passive"))
      (node (ref "U7") (pin "6") (pinfunction "D2-P_6") (pintype "passive"))
    )
    (net (code "32") (name "Net-(D3-C1)") (class "Default")
      (node (ref "D3") (pin "5") (pinfunction "C1_5") (pintype "passive"))
      (node (ref "U6") (pin "7") (pinfunction "D1-N_7") (pintype "passive"))
      (node (ref "U6") (pin "8") (pinfunction "D1-N_8") (pintype "passive"))
    )
    (net (code "33") (name "Net-(D3-C2)") (class "Default")
      (node (ref "D3") (pin "4") (pinfunction "C2_4") (pintype "passive"))
      (node (ref "U7") (pin "7") (pinfunction "D1-N_7") (pintype "passive"))
      (node (ref "U7") (pin "8") (pinfunction "D1-N_8") (pintype "passive"))
    )
    (net (code "34") (name "Net-(D10-A)") (class "Default")
      (node (ref "D10") (pin "1") (pinfunction "A_1") (pintype "passive"))
      (node (ref "D10") (pin "2") (pinfunction "K_2") (pintype "passive"))
      (node (ref "J9") (pin "1") (pinfunction "X_1") (pintype "passive"))
      (node (ref "U8") (pin "3") (pinfunction "B_3") (pintype "passive"))
    )
    (net (code "35") (name "Net-(J5-Pad2)") (class "Default")
      (node (ref "J5") (pin "2") (pinfunction "2_2") (pintype "passive"))
      (node (ref "R1") (pin "1") (pinfunction "1_1") (pintype "passive"))
    )
    (net (code "36") (name "Net-(J6-Pad4)") (class "Default")
      (node (ref "J6") (pin "4") (pinfunction "4_4") (pintype "passive"))
      (node (ref "R2") (pin "1") (pinfunction "1_1") (pintype "passive"))
    )
    (net (code "37") (name "Net-(J7-X)") (class "Default")
      (node (ref "J7") (pin "1") (pinfunction "X_1") (pintype "passive"))
      (node (ref "R1") (pin "2") (pinfunction "2_2") (pintype "passive"))
      (node (ref "TX1") (pin "1") (pinfunction "1_1") (pintype "passive"))
    )
    (net (code "38") (name "Net-(J8-X)") (class "Default")
      (node (ref "J8") (pin "1") (pinfunction "X_1") (pintype "passive"))
      (node (ref "R2") (pin "2") (pinfunction "2_2") (pintype "passive"))
      (node (ref "TX2") (pin "1") (pinfunction "1_1") (pintype "passive"))
      (node (ref "U8") (pin "1") (pinfunction "A_1") (pintype "passive"))
    )
    (net (code "39") (name "Net-(U1-AVDD1)") (class "Default")
      (node (ref "C31") (pin "2") (pinfunction "2_2") (pintype "passive"))
      (node (ref "FB1") (pin "1") (pinfunction "1_1") (pintype "passive"))
      (node (ref "U1") (pin "6") (pinfunction "AVDD1_6") (pintype "power_in"))
    )
    (net (code "40") (name "Net-(U1-OUTNA1)") (class "Default")
      (node (ref "C2") (pin "1") (pinfunction "1_1") (pintype "passive"))
      (node (ref "U1") (pin "37") (pinfunction "OUTNA1_37") (pintype "passive"))
    )
    (net (code "41") (name "Net-(U1-OUTNA2)") (class "Default")
      (node (ref "C3") (pin "1") (pinfunction "1_1") (pintype "passive"))
      (node (ref "U1") (pin "34") (pinfunction "OUTNA2_34") (pintype "passive"))
    )
    (net (code "42") (name "Net-(U1-OUTNA3)") (class "Default")
      (node (ref "U1") (pin "32") (pinfunction "OUTNA3_32") (pintype "passive"))
      (node (ref "U4") (pin "2") (pinfunction "G1-N_2") (pintype "passive"))
    )
    (net (code "43") (name "Net-(U1-OUTNB1)") (class "Default")
      (node (ref "C5") (pin "1") (pinfunction "1_1") (pintype "passive"))
      (node (ref "U1") (pin "24") (pinfunction "OUTNB1_24") (pintype "passive"))
    )
    (net (code "44") (name "Net-(U1-OUTNB2)") (class "Default")
      (node (ref "C7") (pin "1") (pinfunction "1_1") (pintype "passive"))
      (node (ref "U1") (pin "27") (pinfunction "OUTNB2_27") (pintype "passive"))
    )
    (net (code "45") (name "Net-(U1-OUTNB3)") (class "Default")
      (node (ref "U1") (pin "29") (pinfunction "OUTNB3_29") (pintype "passive"))
      (node (ref "U5") (pin "2") (pinfunction "G1-N_2") (pintype "passive"))
    )
    (net (code "46") (name "Net-(U1-OUTPA1)") (class "Default")
      (node (ref "C1") (pin "1") (pinfunction "1_1") (pintype "passive"))
      (node (ref "U1") (pin "39") (pinfunction "OUTPA1_39") (pintype "passive"))
    )
    (net (code "47") (name "Net-(U1-OUTPA2)") (class "Default")
      (node (ref "C4") (pin "1") (pinfunction "1_1") (pintype "passive"))
      (node (ref "U1") (pin "41") (pinfunction "OUTPA2_41") (pintype "passive"))
    )
    (net (code "48") (name "Net-(U1-OUTPA3)") (class "Default")
      (node (ref "U1") (pin "44") (pinfunction "OUTPA3_44") (pintype "passive"))
      (node (ref "U4") (pin "4") (pinfunction "G2-P_4") (pintype "passive"))
    )
    (net (code "49") (name "Net-(U1-OUTPB1)") (class "Default")
      (node (ref "C6") (pin "1") (pinfunction "1_1") (pintype "passive"))
      (node (ref "U1") (pin "22") (pinfunction "OUTPB1_22") (pintype "passive"))
    )
    (net (code "50") (name "Net-(U1-OUTPB2)") (class "Default")
      (node (ref "C8") (pin "1") (pinfunction "1_1") (pintype "passive"))
      (node (ref "U1") (pin "20") (pinfunction "OUTPB2_20") (pintype "passive"))
    )
    (net (code "51") (name "Net-(U1-OUTPB3)") (class "Default")
      (node (ref "U1") (pin "17") (pinfunction "OUTPB3_17") (pintype "passive"))
      (node (ref "U5") (pin "4") (pinfunction "G2-P_4") (pintype "passive"))
    )
    (net (code "52") (name "Net-(U2-G1-N)") (class "Default")
      (node (ref "C2") (pin "2") (pinfunction "2_2") (pintype "passive"))
      (node (ref "U2") (pin "2") (pinfunction "G1-N_2") (pintype "passive"))
    )
    (net (code "53") (name "Net-(U2-G2-P)") (class "Default")
      (node (ref "C1") (pin "2") (pinfunction "2_2") (pintype "passive"))
      (node (ref "U2") (pin "4") (pinfunction "G2-P_4") (pintype "passive"))
    )
    (net (code "54") (name "Net-(U3-G1-N)") (class "Default")
      (node (ref "C3") (pin "2") (pinfunction "2_2") (pintype "passive"))
      (node (ref "U3") (pin "2") (pinfunction "G1-N_2") (pintype "passive"))
    )
    (net (code "55") (name "Net-(U3-G2-P)") (class "Default")
      (node (ref "C4") (pin "2") (pinfunction "2_2") (pintype "passive"))
      (node (ref "U3") (pin "4") (pinfunction "G2-P_4") (pintype "passive"))
    )
    (net (code "56") (name "Net-(U6-G1-N)") (class "Default")
      (node (ref "C5") (pin "2") (pinfunction "2_2") (pintype "passive"))
      (node (ref "U6") (pin "2") (pinfunction "G1-N_2") (pintype "passive"))
    )
    (net (code "57") (name "Net-(U6-G2-P)") (class "Default")
      (node (ref "C6") (pin "2") (pinfunction "2_2") (pintype "passive"))
      (node (ref "U6") (pin "4") (pinfunction "G2-P_4") (pintype "passive"))
    )
    (net (code "58") (name "Net-(U7-G1-N)") (class "Default")
      (node (ref "C7") (pin "2") (pinfunction "2_2") (pintype "passive"))
      (node (ref "U7") (pin "2") (pinfunction "G1-N_2") (pintype "passive"))
    )
    (net (code "59") (name "Net-(U7-G2-P)") (class "Default")
      (node (ref "C8") (pin "2") (pinfunction "2_2") (pintype "passive"))
      (node (ref "U7") (pin "4") (pinfunction "G2-P_4") (pintype "passive"))
    )
    (net (code "60") (name "VCC") (class "Default")
      (node (ref "C21") (pin "2") (pinfunction "2_2") (pintype "passive"))
      (node (ref "C32") (pin "2") (pinfunction "2_2") (pintype "passive"))
      (node (ref "D8") (pin "1") (pinfunction "A2_1") (pintype "passive"))
      (node (ref "D8") (pin "3") (pinfunction "A1_3") (pintype "passive"))
      (node (ref "J1") (pin "5") (pinfunction "5_5") (pintype "passive"))
      (node (ref "J4") (pin "1") (pinfunction "1_1") (pintype "passive"))
      (node (ref "U1") (pin "46") (pinfunction "VLL_46") (pintype "passive"))
    )
    (net (code "61") (name "VNN1") (class "Default")
      (node (ref "C10") (pin "1") (pinfunction "1_1") (pintype "passive"))
      (node (ref "C14") (pin "2") (pinfunction "2_2") (pintype "passive"))
      (node (ref "C18") (pin "2") (pinfunction "2_2") (pintype "passive"))
      (node (ref "D5") (pin "1") (pinfunction "1_1") (pintype "passive"))
      (node (ref "J3") (pin "1") (pinfunction "1_1") (pintype "passive"))
      (node (ref "U2") (pin "1") (pinfunction "S1-N_1") (pintype "passive"))
      (node (ref "U6") (pin "1") (pinfunction "S1-N_1") (pintype "passive"))
    )
    (net (code "62") (name "VNN2") (class "Default")
      (node (ref "C12") (pin "2") (pinfunction "2_2") (pintype "passive"))
      (node (ref "C16") (pin "2") (pinfunction "2_2") (pintype "passive"))
      (node (ref "C20") (pin "2") (pinfunction "2_2") (pintype "passive"))
      (node (ref "D6") (pin "1") (pinfunction "1_1") (pintype "passive"))
      (node (ref "J2") (pin "1") (pinfunction "1_1") (pintype "passive"))
      (node (ref "U3") (pin "1") (pinfunction "S1-N_1") (pintype "passive"))
      (node (ref "U7") (pin "1") (pinfunction "S1-N_1") (pintype "passive"))
    )
    (net (code "63") (name "VPP1") (class "Default")
      (node (ref "C13") (pin "2") (pinfunction "2_2") (pintype "passive"))
      (node (ref "C17") (pin "2") (pinfunction "2_2") (pintype "passive"))
      (node (ref "C9") (pin "2") (pinfunction "2_2") (pintype "passive"))
      (node (ref "D4") (pin "2") (pinfunction "2_2") (pintype "passive"))
      (node (ref "J3") (pin "3") (pinfunction "3_3") (pintype "power_in"))
      (node (ref "U2") (pin "3") (pinfunction "S2-P_3") (pintype "passive"))
      (node (ref "U6") (pin "3") (pinfunction "S2-P_3") (pintype "passive"))
    )
    (net (code "64") (name "VPP2") (class "Default")
      (node (ref "C11") (pin "2") (pinfunction "2_2") (pintype "passive"))
      (node (ref "C15") (pin "2") (pinfunction "2_2") (pintype "passive"))
      (node (ref "C19") (pin "2") (pinfunction "2_2") (pintype "passive"))
      (node (ref "D7") (pin "2") (pinfunction "2_2") (pintype "passive"))
      (node (ref "J2") (pin "3") (pinfunction "3_3") (pintype "power_in"))
      (node (ref "U3") (pin "3") (pinfunction "S2-P_3") (pintype "passive"))
      (node (ref "U7") (pin "3") (pinfunction "S2-P_3") (pintype "passive"))
    )
    (net (code "65") (name "unconnected-(U1-NC1-Pad23)") (class "Default")
      (node (ref "U1") (pin "23") (pinfunction "NC1_23") (pintype "passive+no_connect"))
    )
    (net (code "66") (name "unconnected-(U1-NC2-Pad38)") (class "Default")
      (node (ref "U1") (pin "38") (pinfunction "NC2_38") (pintype "passive+no_connect"))
    )
    (net (code "67") (name "unconnected-(U8-COM-Pad2)") (class "Default")
      (node (ref "U8") (pin "2") (pinfunction "COM_2") (pintype "passive+no_connect"))
    )
  )
)
